# AnalogClock.net
KiCad netlist of a schematic drawn in EAGLE
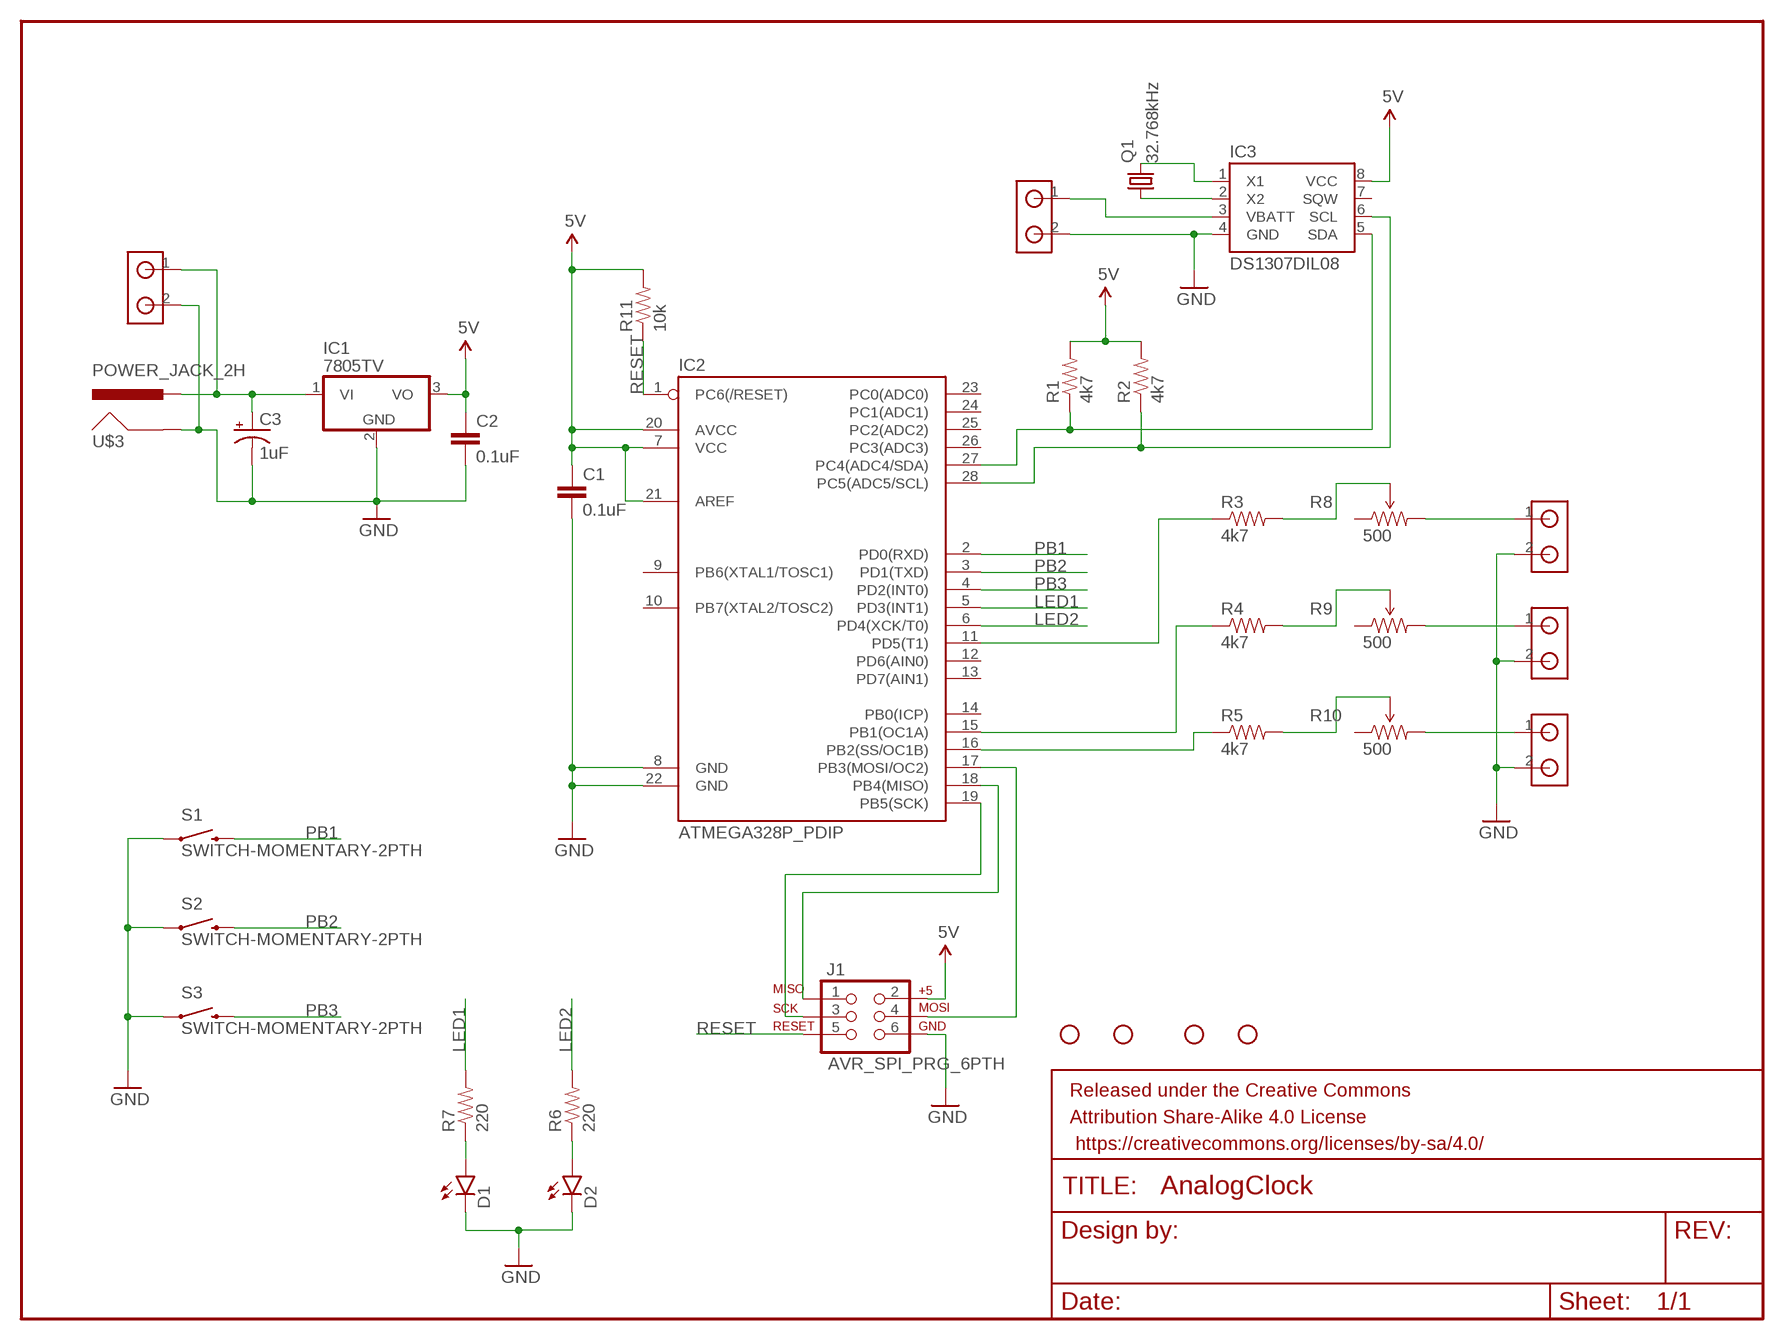
[diagram p0: schematic, sheet 1]

(export (version "E")
  (design (tool "Eeschema 10.0.6"))
  (components
    (comp (ref "C1")
      (value "0.1uF")
      (footprint "eagle-import:CAP-PTH-SMALL")
      (libsource (lib "eagle-import") (part "CAPPTH"))
    )
    (comp (ref "C2")
      (value "0.1uF")
      (footprint "eagle-import:CAP-PTH-SMALL")
      (libsource (lib "eagle-import") (part "CAPPTH"))
    )
    (comp (ref "C3")
      (value "1uF")
      (footprint "eagle-import:CPOL-RADIAL-10UF-25V")
      (libsource (lib "eagle-import") (part "CAP_POLPTH2"))
    )
    (comp (ref "D1")
      (value "LED3MM")
      (footprint "eagle-import:LED3MM")
      (libsource (lib "eagle-import") (part "LED3MM"))
    )
    (comp (ref "D2")
      (value "LED3MM")
      (footprint "eagle-import:LED3MM")
      (libsource (lib "eagle-import") (part "LED3MM"))
    )
    (comp (ref "FRAME1")
      (value "FRAME-LETTERNO_PACKAGE")
      (footprint "eagle-import:DUMMY")
      (fields (field (name "DESIGNER") "Nobody"))
      (libsource (lib "eagle-import") (part "FRAME-LETTERNO_PACKAGE"))
    )
    (comp (ref "H1")
      (value "STAND-OFF")
      (footprint "eagle-import:STAND-OFF")
      (libsource (lib "eagle-import") (part "STAND-OFF"))
    )
    (comp (ref "H2")
      (value "STAND-OFF")
      (footprint "eagle-import:STAND-OFF")
      (libsource (lib "eagle-import") (part "STAND-OFF"))
    )
    (comp (ref "H3")
      (value "STAND-OFF")
      (footprint "eagle-import:STAND-OFF")
      (libsource (lib "eagle-import") (part "STAND-OFF"))
    )
    (comp (ref "H4")
      (value "STAND-OFF")
      (footprint "eagle-import:STAND-OFF")
      (libsource (lib "eagle-import") (part "STAND-OFF"))
    )
    (comp (ref "IC1")
      (value "7805TV")
      (footprint "eagle-import:TO220V")
      (libsource (lib "eagle-import") (part "78TV05"))
    )
    (comp (ref "IC2")
      (value "ATMEGA328P_PDIP")
      (footprint "eagle-import:DIL28-3")
      (libsource (lib "eagle-import") (part "ATMEGA328P_PDIP"))
    )
    (comp (ref "IC3")
      (value "DS1307DIL08")
      (footprint "eagle-import:DIL08")
      (libsource (lib "eagle-import") (part "DS1307DIL08"))
    )
    (comp (ref "J1")
      (value "AVR_SPI_PRG_6PTH")
      (footprint "eagle-import:2X3")
      (libsource (lib "eagle-import") (part "AVR_SPI_PRG_6PTH"))
    )
    (comp (ref "Q1")
      (value "32.768kHz")
      (footprint "eagle-import:TC26V")
      (libsource (lib "eagle-import") (part "CRYSTALTC26V"))
    )
    (comp (ref "R1")
      (value "4k7")
      (footprint "eagle-import:AXIAL-0.4")
      (libsource (lib "eagle-import") (part "RESISTORPTH-1/4W"))
    )
    (comp (ref "R2")
      (value "4k7")
      (footprint "eagle-import:AXIAL-0.4")
      (libsource (lib "eagle-import") (part "RESISTORPTH-1/4W"))
    )
    (comp (ref "R3")
      (value "4k7")
      (footprint "eagle-import:AXIAL-0.4")
      (libsource (lib "eagle-import") (part "RESISTORPTH-1/4W"))
    )
    (comp (ref "R4")
      (value "4k7")
      (footprint "eagle-import:AXIAL-0.4")
      (libsource (lib "eagle-import") (part "RESISTORPTH-1/4W"))
    )
    (comp (ref "R5")
      (value "4k7")
      (footprint "eagle-import:AXIAL-0.4")
      (libsource (lib "eagle-import") (part "RESISTORPTH-1/4W"))
    )
    (comp (ref "R6")
      (value "220")
      (footprint "eagle-import:AXIAL-0.4")
      (libsource (lib "eagle-import") (part "RESISTORPTH-1/4W"))
    )
    (comp (ref "R7")
      (value "220")
      (footprint "eagle-import:AXIAL-0.4")
      (libsource (lib "eagle-import") (part "RESISTORPTH-1/4W"))
    )
    (comp (ref "R8")
      (value "500")
      (footprint "eagle-import:TRIMPOT")
      (libsource (lib "eagle-import") (part "TRIMPOT"))
    )
    (comp (ref "R9")
      (value "500")
      (footprint "eagle-import:TRIMPOT")
      (libsource (lib "eagle-import") (part "TRIMPOT"))
    )
    (comp (ref "R10")
      (value "500")
      (footprint "eagle-import:TRIMPOT")
      (libsource (lib "eagle-import") (part "TRIMPOT"))
    )
    (comp (ref "R11")
      (value "10k")
      (footprint "eagle-import:AXIAL-0.4")
      (libsource (lib "eagle-import") (part "RESISTORPTH-1/4W"))
    )
    (comp (ref "S1")
      (value "SWITCH-MOMENTARY-2PTH")
      (footprint "eagle-import:TACTILE-PTH")
      (libsource (lib "eagle-import") (part "SWITCH-MOMENTARY-2PTH"))
    )
    (comp (ref "S2")
      (value "SWITCH-MOMENTARY-2PTH")
      (footprint "eagle-import:TACTILE-PTH")
      (libsource (lib "eagle-import") (part "SWITCH-MOMENTARY-2PTH"))
    )
    (comp (ref "S3")
      (value "SWITCH-MOMENTARY-2PTH")
      (footprint "eagle-import:TACTILE-PTH")
      (libsource (lib "eagle-import") (part "SWITCH-MOMENTARY-2PTH"))
    )
    (comp (ref "U$1")
      (value "TBLOCK")
      (footprint "eagle-import:TBLOCK")
      (libsource (lib "eagle-import") (part "TBLOCK"))
    )
    (comp (ref "U$3")
      (value "POWER_JACK_2H")
      (footprint "eagle-import:POWER_JACK_2H")
      (libsource (lib "eagle-import") (part "POWER_JACK_2H"))
    )
    (comp (ref "U$4")
      (value "TBLOCK")
      (footprint "eagle-import:TBLOCK")
      (libsource (lib "eagle-import") (part "TBLOCK"))
    )
    (comp (ref "U$5")
      (value "TBLOCK")
      (footprint "eagle-import:TBLOCK")
      (libsource (lib "eagle-import") (part "TBLOCK"))
    )
    (comp (ref "U$6")
      (value "TBLOCK")
      (footprint "eagle-import:TBLOCK")
      (libsource (lib "eagle-import") (part "TBLOCK"))
    )
    (comp (ref "U$7")
      (value "TBLOCK")
      (footprint "eagle-import:TBLOCK")
      (libsource (lib "eagle-import") (part "TBLOCK"))
    )
  )
  (nets
    (net (code "1") (name "/LED1") (class "Default")
      (node (ref "IC2") (pin "5") (pinfunction "PD3(INT1)_5") (pintype "bidirectional"))
      (node (ref "R7") (pin "P$2") (pinfunction "2_P$2") (pintype "passive"))
    )
    (net (code "2") (name "/LED2") (class "Default")
      (node (ref "IC2") (pin "6") (pinfunction "PD4(XCK/T0)_6") (pintype "bidirectional"))
      (node (ref "R6") (pin "P$2") (pinfunction "2_P$2") (pintype "passive"))
    )
    (net (code "3") (name "/PB1") (class "Default")
      (node (ref "IC2") (pin "2") (pinfunction "PD0(RXD)_2") (pintype "bidirectional"))
      (node (ref "S1") (pin "3") (pinfunction "2_3") (pintype "passive"))
    )
    (net (code "4") (name "/PB2") (class "Default")
      (node (ref "IC2") (pin "3") (pinfunction "PD1(TXD)_3") (pintype "bidirectional"))
      (node (ref "S2") (pin "3") (pinfunction "2_3") (pintype "passive"))
    )
    (net (code "5") (name "/PB3") (class "Default")
      (node (ref "IC2") (pin "4") (pinfunction "PD2(INT0)_4") (pintype "bidirectional"))
      (node (ref "S3") (pin "3") (pinfunction "2_3") (pintype "passive"))
    )
    (net (code "6") (name "/RESET") (class "Default")
      (node (ref "IC2") (pin "1") (pinfunction "PC6(/RESET)_1") (pintype "bidirectional"))
      (node (ref "J1") (pin "5") (pinfunction "5_5") (pintype "passive"))
      (node (ref "R11") (pin "P$1") (pinfunction "1_P$1") (pintype "passive"))
    )
    (net (code "7") (name "5V") (class "Default")
      (node (ref "C1") (pin "1") (pinfunction "1_1") (pintype "passive"))
      (node (ref "C2") (pin "1") (pinfunction "1_1") (pintype "passive"))
      (node (ref "IC1") (pin "3") (pinfunction "VO_3") (pintype "passive"))
      (node (ref "IC2") (pin "20") (pinfunction "AVCC_20") (pintype "bidirectional"))
      (node (ref "IC2") (pin "21") (pinfunction "AREF_21") (pintype "bidirectional"))
      (node (ref "IC2") (pin "7") (pinfunction "VCC_7") (pintype "bidirectional"))
      (node (ref "IC3") (pin "8") (pinfunction "VCC_8") (pintype "bidirectional"))
      (node (ref "J1") (pin "2") (pinfunction "2_2") (pintype "passive"))
      (node (ref "R1") (pin "P$2") (pinfunction "2_P$2") (pintype "passive"))
      (node (ref "R11") (pin "P$2") (pinfunction "2_P$2") (pintype "passive"))
      (node (ref "R2") (pin "P$2") (pinfunction "2_P$2") (pintype "passive"))
    )
    (net (code "8") (name "GND") (class "Default")
      (node (ref "C1") (pin "2") (pinfunction "2_2") (pintype "passive"))
      (node (ref "C2") (pin "2") (pinfunction "2_2") (pintype "passive"))
      (node (ref "C3") (pin "2") (pinfunction "-_2") (pintype "passive"))
      (node (ref "D1") (pin "K") (pinfunction "C_K") (pintype "passive"))
      (node (ref "D2") (pin "K") (pinfunction "C_K") (pintype "passive"))
      (node (ref "IC1") (pin "2") (pinfunction "GND_2") (pintype "passive"))
      (node (ref "IC2") (pin "22") (pinfunction "GND_22") (pintype "bidirectional"))
      (node (ref "IC2") (pin "8") (pinfunction "GND_8") (pintype "bidirectional"))
      (node (ref "IC3") (pin "4") (pinfunction "GND_4") (pintype "bidirectional"))
      (node (ref "J1") (pin "6") (pinfunction "6_6") (pintype "passive"))
      (node (ref "S1") (pin "1") (pinfunction "1_1") (pintype "passive"))
      (node (ref "S2") (pin "1") (pinfunction "1_1") (pintype "passive"))
      (node (ref "S3") (pin "1") (pinfunction "1_1") (pintype "passive"))
      (node (ref "U$1") (pin "2") (pinfunction "2_2") (pintype "bidirectional"))
      (node (ref "U$3") (pin "P$1") (pinfunction "GND_P$1") (pintype "bidirectional"))
      (node (ref "U$4") (pin "2") (pinfunction "2_2") (pintype "bidirectional"))
      (node (ref "U$5") (pin "2") (pinfunction "2_2") (pintype "bidirectional"))
      (node (ref "U$6") (pin "2") (pinfunction "2_2") (pintype "bidirectional"))
      (node (ref "U$7") (pin "2") (pinfunction "2_2") (pintype "bidirectional"))
    )
    (net (code "9") (name "Net-(C3-+)") (class "Default")
      (node (ref "C3") (pin "1") (pinfunction "+_1") (pintype "passive"))
      (node (ref "IC1") (pin "1") (pinfunction "VI_1") (pintype "input"))
      (node (ref "U$3") (pin "P$2") (pinfunction "PWR_P$2") (pintype "bidirectional"))
      (node (ref "U$5") (pin "1") (pinfunction "1_1") (pintype "bidirectional"))
    )
    (net (code "10") (name "Net-(IC2-PB1(OC1A))") (class "Default")
      (node (ref "IC2") (pin "15") (pinfunction "PB1(OC1A)_15") (pintype "bidirectional"))
      (node (ref "R4") (pin "P$1") (pinfunction "1_P$1") (pintype "passive"))
    )
    (net (code "11") (name "Net-(IC2-PB2(SS{slash}OC1B))") (class "Default")
      (node (ref "IC2") (pin "16") (pinfunction "PB2(SS/OC1B)_16") (pintype "bidirectional"))
      (node (ref "R5") (pin "P$1") (pinfunction "1_P$1") (pintype "passive"))
    )
    (net (code "12") (name "Net-(IC2-PB3(MOSI{slash}OC2))") (class "Default")
      (node (ref "IC2") (pin "17") (pinfunction "PB3(MOSI/OC2)_17") (pintype "bidirectional"))
      (node (ref "J1") (pin "4") (pinfunction "4_4") (pintype "passive"))
    )
    (net (code "13") (name "Net-(IC2-PB4(MISO))") (class "Default")
      (node (ref "IC2") (pin "18") (pinfunction "PB4(MISO)_18") (pintype "bidirectional"))
      (node (ref "J1") (pin "1") (pinfunction "1_1") (pintype "passive"))
    )
    (net (code "14") (name "Net-(IC2-PB5(SCK))") (class "Default")
      (node (ref "IC2") (pin "19") (pinfunction "PB5(SCK)_19") (pintype "bidirectional"))
      (node (ref "J1") (pin "3") (pinfunction "3_3") (pintype "passive"))
    )
    (net (code "15") (name "Net-(IC2-PC4(ADC4{slash}SDA))") (class "Default")
      (node (ref "IC2") (pin "27") (pinfunction "PC4(ADC4/SDA)_27") (pintype "bidirectional"))
      (node (ref "IC3") (pin "5") (pinfunction "SDA_5") (pintype "bidirectional"))
      (node (ref "R1") (pin "P$1") (pinfunction "1_P$1") (pintype "passive"))
    )
    (net (code "16") (name "Net-(IC2-PC5(ADC5{slash}SCL))") (class "Default")
      (node (ref "IC2") (pin "28") (pinfunction "PC5(ADC5/SCL)_28") (pintype "bidirectional"))
      (node (ref "IC3") (pin "6") (pinfunction "SCL_6") (pintype "bidirectional"))
      (node (ref "R2") (pin "P$1") (pinfunction "1_P$1") (pintype "passive"))
    )
    (net (code "17") (name "Net-(IC2-PD5(T1))") (class "Default")
      (node (ref "IC2") (pin "11") (pinfunction "PD5(T1)_11") (pintype "bidirectional"))
      (node (ref "R3") (pin "P$1") (pinfunction "1_P$1") (pintype "passive"))
    )
    (net (code "18") (name "Net-(IC3-VBATT)") (class "Default")
      (node (ref "IC3") (pin "3") (pinfunction "VBATT_3") (pintype "bidirectional"))
      (node (ref "U$1") (pin "1") (pinfunction "1_1") (pintype "bidirectional"))
    )
    (net (code "19") (name "Net-(IC3-X1)") (class "Default")
      (node (ref "IC3") (pin "1") (pinfunction "X1_1") (pintype "bidirectional"))
      (node (ref "Q1") (pin "2") (pinfunction "2_2") (pintype "passive"))
    )
    (net (code "20") (name "Net-(IC3-X2)") (class "Default")
      (node (ref "IC3") (pin "2") (pinfunction "X2_2") (pintype "bidirectional"))
      (node (ref "Q1") (pin "1") (pinfunction "1_1") (pintype "passive"))
    )
    (net (code "21") (name "Net-(R3-2)") (class "Default")
      (node (ref "R3") (pin "P$2") (pinfunction "2_P$2") (pintype "passive"))
      (node (ref "R8") (pin "P$3") (pinfunction "WIPER_P$3") (pintype "passive"))
    )
    (net (code "22") (name "Net-(R4-2)") (class "Default")
      (node (ref "R4") (pin "P$2") (pinfunction "2_P$2") (pintype "passive"))
      (node (ref "R9") (pin "P$3") (pinfunction "WIPER_P$3") (pintype "passive"))
    )
    (net (code "23") (name "Net-(R6-1)") (class "Default")
      (node (ref "D2") (pin "A") (pinfunction "A_A") (pintype "passive"))
      (node (ref "R6") (pin "P$1") (pinfunction "1_P$1") (pintype "passive"))
    )
    (net (code "24") (name "Net-(R7-1)") (class "Default")
      (node (ref "D1") (pin "A") (pinfunction "A_A") (pintype "passive"))
      (node (ref "R7") (pin "P$1") (pinfunction "1_P$1") (pintype "passive"))
    )
    (net (code "25") (name "Net-(R8-CW)") (class "Default")
      (node (ref "R8") (pin "P$2") (pinfunction "CW_P$2") (pintype "passive"))
      (node (ref "U$4") (pin "1") (pinfunction "1_1") (pintype "bidirectional"))
    )
    (net (code "26") (name "Net-(R9-CW)") (class "Default")
      (node (ref "R9") (pin "P$2") (pinfunction "CW_P$2") (pintype "passive"))
      (node (ref "U$6") (pin "1") (pinfunction "1_1") (pintype "bidirectional"))
    )
    (net (code "27") (name "Net-(R10-CW)") (class "Default")
      (node (ref "R10") (pin "P$2") (pinfunction "CW_P$2") (pintype "passive"))
      (node (ref "U$7") (pin "1") (pinfunction "1_1") (pintype "bidirectional"))
    )
    (net (code "28") (name "Net-(R10-WIPER)") (class "Default")
      (node (ref "R10") (pin "P$3") (pinfunction "WIPER_P$3") (pintype "passive"))
      (node (ref "R5") (pin "P$2") (pinfunction "2_P$2") (pintype "passive"))
    )
    (net (code "29") (name "unconnected-(IC2-PB0(ICP)-Pad14)") (class "Default")
      (node (ref "IC2") (pin "14") (pinfunction "PB0(ICP)_14") (pintype "bidirectional"))
    )
    (net (code "30") (name "unconnected-(IC2-PB6(XTAL1{slash}TOSC1)-Pad9)") (class "Default")
      (node (ref "IC2") (pin "9") (pinfunction "PB6(XTAL1/TOSC1)_9") (pintype "bidirectional"))
    )
    (net (code "31") (name "unconnected-(IC2-PB7(XTAL2{slash}TOSC2)-Pad10)") (class "Default")
      (node (ref "IC2") (pin "10") (pinfunction "PB7(XTAL2/TOSC2)_10") (pintype "bidirectional"))
    )
    (net (code "32") (name "unconnected-(IC2-PC0(ADC0)-Pad23)") (class "Default")
      (node (ref "IC2") (pin "23") (pinfunction "PC0(ADC0)_23") (pintype "bidirectional"))
    )
    (net (code "33") (name "unconnected-(IC2-PC1(ADC1)-Pad24)") (class "Default")
      (node (ref "IC2") (pin "24") (pinfunction "PC1(ADC1)_24") (pintype "bidirectional"))
    )
    (net (code "34") (name "unconnected-(IC2-PC2(ADC2)-Pad25)") (class "Default")
      (node (ref "IC2") (pin "25") (pinfunction "PC2(ADC2)_25") (pintype "bidirectional"))
    )
    (net (code "35") (name "unconnected-(IC2-PC3(ADC3)-Pad26)") (class "Default")
      (node (ref "IC2") (pin "26") (pinfunction "PC3(ADC3)_26") (pintype "bidirectional"))
    )
    (net (code "36") (name "unconnected-(IC2-PD6(AIN0)-Pad12)") (class "Default")
      (node (ref "IC2") (pin "12") (pinfunction "PD6(AIN0)_12") (pintype "bidirectional"))
    )
    (net (code "37") (name "unconnected-(IC2-PD7(AIN1)-Pad13)") (class "Default")
      (node (ref "IC2") (pin "13") (pinfunction "PD7(AIN1)_13") (pintype "bidirectional"))
    )
    (net (code "38") (name "unconnected-(IC3-SQW-Pad7)") (class "Default")
      (node (ref "IC3") (pin "7") (pinfunction "SQW_7") (pintype "bidirectional"))
    )
    (net (code "39") (name "unconnected-(R8-CCW-PadP$1)") (class "Default")
      (node (ref "R8") (pin "P$1") (pinfunction "CCW_P$1") (pintype "passive"))
    )
    (net (code "40") (name "unconnected-(R9-CCW-PadP$1)") (class "Default")
      (node (ref "R9") (pin "P$1") (pinfunction "CCW_P$1") (pintype "passive"))
    )
    (net (code "41") (name "unconnected-(R10-CCW-PadP$1)") (class "Default")
      (node (ref "R10") (pin "P$1") (pinfunction "CCW_P$1") (pintype "passive"))
    )
  )
)
